# USB_Booster.net
KiCad netlist of a schematic drawn in Altium Designer
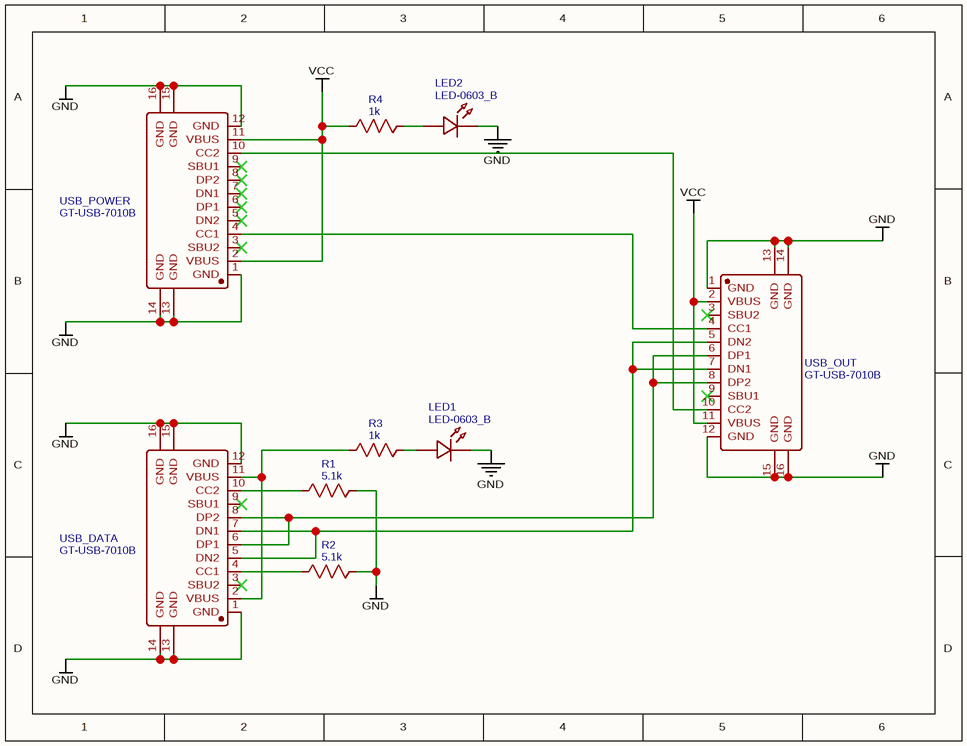
[diagram p0: USB_Booster.schdoc]

(export (version "E")
  (design (tool "Eeschema 10.0.6"))
  (components
    (comp (ref "LED1")
      (value "LED-0603_B")
      (fields
        (field (name "BOM_MANUFACTURER PART") "19-217/BHC-ZL1M2RY/3T")
        (field (name "BOM_SUPPLIER PART") "C72041")
        (field (name "CONTRIBUTOR") "LCEDA_01")
      )
      (libsource (lib "altium-import") (part "root_0_LED-0603_B_"))
    )
    (comp (ref "LED2")
      (value "LED-0603_B")
      (fields
        (field (name "BOM_MANUFACTURER PART") "19-217/BHC-ZL1M2RY/3T")
        (field (name "BOM_SUPPLIER PART") "C72041")
        (field (name "CONTRIBUTOR") "LCEDA_01")
      )
      (libsource (lib "altium-import") (part "root_0_LED-0603_B_"))
    )
    (comp (ref "R1")
      (value "5.1k")
      (fields (field (name "CONTRIBUTOR") "LCEDA_Lib"))
      (libsource (lib "altium-import") (part "root_0_5.1k_"))
    )
    (comp (ref "R2")
      (value "5.1k")
      (fields (field (name "CONTRIBUTOR") "LCEDA_Lib"))
      (libsource (lib "altium-import") (part "root_0_5.1k_"))
    )
    (comp (ref "R3")
      (value "1k")
      (fields (field (name "CONTRIBUTOR") "LCEDA_Lib"))
      (libsource (lib "altium-import") (part "root_0_1k_"))
    )
    (comp (ref "R4")
      (value "1k")
      (fields (field (name "CONTRIBUTOR") "LCEDA_Lib"))
      (libsource (lib "altium-import") (part "root_0_1k_"))
    )
    (comp (ref "USB_DATA")
      (value "GT-USB-7010B")
      (fields (field (name "BOM_SUPPLIER PART") "C2837092") (field (name "CONTRIBUTOR") "LCSC"))
      (libsource (lib "altium-import") (part "root_2_GT-USB-7010B_"))
    )
    (comp (ref "USB_OUT")
      (value "GT-USB-7010B")
      (fields (field (name "BOM_SUPPLIER PART") "C2837092") (field (name "CONTRIBUTOR") "LCSC"))
      (libsource (lib "altium-import") (part "root_0_GT-USB-7010B_"))
    )
    (comp (ref "USB_POWER")
      (value "GT-USB-7010B")
      (fields (field (name "BOM_SUPPLIER PART") "C2837092") (field (name "CONTRIBUTOR") "LCSC"))
      (libsource (lib "altium-import") (part "root_2_GT-USB-7010B_"))
    )
  )
  (nets
    (net (code "1") (name "GND") (class "Default")
      (node (ref "LED1") (pin "2") (pinfunction "2_2") (pintype "passive"))
      (node (ref "LED2") (pin "2") (pinfunction "2_2") (pintype "passive"))
      (node (ref "R1") (pin "2") (pinfunction "2_2") (pintype "passive"))
      (node (ref "R2") (pin "2") (pinfunction "2_2") (pintype "passive"))
      (node (ref "USB_DATA") (pin "1") (pinfunction "GND_1") (pintype "passive"))
      (node (ref "USB_DATA") (pin "12") (pinfunction "GND_12") (pintype "passive"))
      (node (ref "USB_DATA") (pin "13") (pinfunction "GND_13") (pintype "passive"))
      (node (ref "USB_DATA") (pin "14") (pinfunction "GND_14") (pintype "passive"))
      (node (ref "USB_DATA") (pin "15") (pinfunction "GND_15") (pintype "passive"))
      (node (ref "USB_DATA") (pin "16") (pinfunction "GND_16") (pintype "passive"))
      (node (ref "USB_OUT") (pin "1") (pinfunction "GND_1") (pintype "passive"))
      (node (ref "USB_OUT") (pin "12") (pinfunction "GND_12") (pintype "passive"))
      (node (ref "USB_OUT") (pin "13") (pinfunction "GND_13") (pintype "passive"))
      (node (ref "USB_OUT") (pin "14") (pinfunction "GND_14") (pintype "passive"))
      (node (ref "USB_OUT") (pin "15") (pinfunction "GND_15") (pintype "passive"))
      (node (ref "USB_OUT") (pin "16") (pinfunction "GND_16") (pintype "passive"))
      (node (ref "USB_POWER") (pin "1") (pinfunction "GND_1") (pintype "passive"))
      (node (ref "USB_POWER") (pin "12") (pinfunction "GND_12") (pintype "passive"))
      (node (ref "USB_POWER") (pin "13") (pinfunction "GND_13") (pintype "passive"))
      (node (ref "USB_POWER") (pin "14") (pinfunction "GND_14") (pintype "passive"))
      (node (ref "USB_POWER") (pin "15") (pinfunction "GND_15") (pintype "passive"))
      (node (ref "USB_POWER") (pin "16") (pinfunction "GND_16") (pintype "passive"))
    )
    (net (code "2") (name "Net-(LED1-Pad1)") (class "Default")
      (node (ref "LED1") (pin "1") (pinfunction "1_1") (pintype "passive"))
      (node (ref "R3") (pin "2") (pinfunction "2_2") (pintype "passive"))
    )
    (net (code "3") (name "Net-(LED2-Pad1)") (class "Default")
      (node (ref "LED2") (pin "1") (pinfunction "1_1") (pintype "passive"))
      (node (ref "R4") (pin "2") (pinfunction "2_2") (pintype "passive"))
    )
    (net (code "4") (name "Net-(R3-Pad1)") (class "Default")
      (node (ref "R3") (pin "1") (pinfunction "1_1") (pintype "passive"))
      (node (ref "USB_DATA") (pin "11") (pinfunction "VBUS_11") (pintype "passive"))
      (node (ref "USB_DATA") (pin "2") (pinfunction "VBUS_2") (pintype "passive"))
    )
    (net (code "5") (name "Net-(USB_DATA-CC1)") (class "Default")
      (node (ref "R2") (pin "1") (pinfunction "1_1") (pintype "passive"))
      (node (ref "USB_DATA") (pin "4") (pinfunction "CC1_4") (pintype "passive"))
    )
    (net (code "6") (name "Net-(USB_DATA-CC2)") (class "Default")
      (node (ref "R1") (pin "1") (pinfunction "1_1") (pintype "passive"))
      (node (ref "USB_DATA") (pin "10") (pinfunction "CC2_10") (pintype "passive"))
    )
    (net (code "7") (name "Net-(USB_DATA-DN1)") (class "Default")
      (node (ref "USB_DATA") (pin "5") (pinfunction "DN2_5") (pintype "passive"))
      (node (ref "USB_DATA") (pin "7") (pinfunction "DN1_7") (pintype "passive"))
      (node (ref "USB_OUT") (pin "5") (pinfunction "DN2_5") (pintype "passive"))
      (node (ref "USB_OUT") (pin "7") (pinfunction "DN1_7") (pintype "passive"))
    )
    (net (code "8") (name "Net-(USB_DATA-DP1)") (class "Default")
      (node (ref "USB_DATA") (pin "6") (pinfunction "DP1_6") (pintype "passive"))
      (node (ref "USB_DATA") (pin "8") (pinfunction "DP2_8") (pintype "passive"))
      (node (ref "USB_OUT") (pin "6") (pinfunction "DP1_6") (pintype "passive"))
      (node (ref "USB_OUT") (pin "8") (pinfunction "DP2_8") (pintype "passive"))
    )
    (net (code "9") (name "Net-(USB_OUT-CC1)") (class "Default")
      (node (ref "USB_OUT") (pin "4") (pinfunction "CC1_4") (pintype "passive"))
      (node (ref "USB_POWER") (pin "4") (pinfunction "CC1_4") (pintype "passive"))
    )
    (net (code "10") (name "Net-(USB_OUT-CC2)") (class "Default")
      (node (ref "USB_OUT") (pin "10") (pinfunction "CC2_10") (pintype "passive"))
      (node (ref "USB_POWER") (pin "10") (pinfunction "CC2_10") (pintype "passive"))
    )
    (net (code "11") (name "VCC") (class "Default")
      (node (ref "R4") (pin "1") (pinfunction "1_1") (pintype "passive"))
      (node (ref "USB_OUT") (pin "11") (pinfunction "VBUS_11") (pintype "passive"))
      (node (ref "USB_OUT") (pin "2") (pinfunction "VBUS_2") (pintype "passive"))
      (node (ref "USB_POWER") (pin "11") (pinfunction "VBUS_11") (pintype "passive"))
      (node (ref "USB_POWER") (pin "2") (pinfunction "VBUS_2") (pintype "passive"))
    )
    (net (code "12") (name "unconnected-(USB_DATA-SBU1-Pad9)") (class "Default")
      (node (ref "USB_DATA") (pin "9") (pinfunction "SBU1_9") (pintype "passive+no_connect"))
    )
    (net (code "13") (name "unconnected-(USB_DATA-SBU2-Pad3)") (class "Default")
      (node (ref "USB_DATA") (pin "3") (pinfunction "SBU2_3") (pintype "passive+no_connect"))
    )
    (net (code "14") (name "unconnected-(USB_OUT-SBU1-Pad9)") (class "Default")
      (node (ref "USB_OUT") (pin "9") (pinfunction "SBU1_9") (pintype "passive+no_connect"))
    )
    (net (code "15") (name "unconnected-(USB_OUT-SBU2-Pad3)") (class "Default")
      (node (ref "USB_OUT") (pin "3") (pinfunction "SBU2_3") (pintype "passive+no_connect"))
    )
    (net (code "16") (name "unconnected-(USB_POWER-DN1-Pad7)") (class "Default")
      (node (ref "USB_POWER") (pin "7") (pinfunction "DN1_7") (pintype "passive+no_connect"))
    )
    (net (code "17") (name "unconnected-(USB_POWER-DN2-Pad5)") (class "Default")
      (node (ref "USB_POWER") (pin "5") (pinfunction "DN2_5") (pintype "passive+no_connect"))
    )
    (net (code "18") (name "unconnected-(USB_POWER-DP1-Pad6)") (class "Default")
      (node (ref "USB_POWER") (pin "6") (pinfunction "DP1_6") (pintype "passive+no_connect"))
    )
    (net (code "19") (name "unconnected-(USB_POWER-DP2-Pad8)") (class "Default")
      (node (ref "USB_POWER") (pin "8") (pinfunction "DP2_8") (pintype "passive+no_connect"))
    )
    (net (code "20") (name "unconnected-(USB_POWER-SBU1-Pad9)") (class "Default")
      (node (ref "USB_POWER") (pin "9") (pinfunction "SBU1_9") (pintype "passive+no_connect"))
    )
    (net (code "21") (name "unconnected-(USB_POWER-SBU2-Pad3)") (class "Default")
      (node (ref "USB_POWER") (pin "3") (pinfunction "SBU2_3") (pintype "passive+no_connect"))
    )
  )
)
